# BMS_watchdog.net
KiCad netlist of a schematic drawn in EAGLE
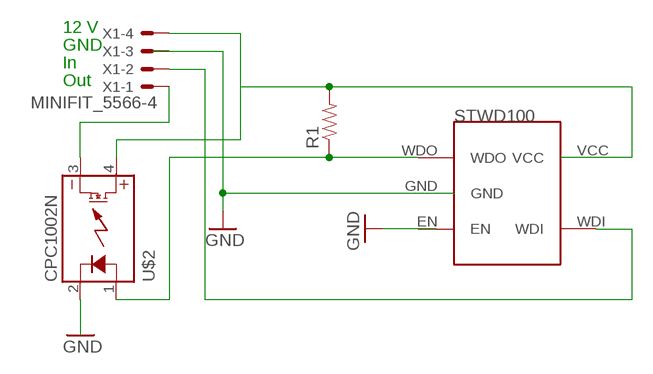
[diagram p0: schematic, sheet 1]

(export (version "E")
  (design (tool "Eeschema 10.0.6"))
  (components
    (comp (ref "R1")
      (value "RESISTOR0805-RES")
      (footprint "eagle-import:0805")
      (libsource (lib "eagle-import") (part "RESISTOR0805-RES"))
    )
    (comp (ref "U$1")
      (value "STWD100")
      (footprint "eagle-import:SOT23-5")
      (libsource (lib "eagle-import") (part "STWD100"))
    )
    (comp (ref "U$2")
      (value "CPC1002N")
      (footprint "eagle-import:SOP04")
      (libsource (lib "eagle-import") (part "CPC1002N"))
    )
    (comp (ref "X1")
      (value "MINIFIT_5566-4")
      (footprint "eagle-import:MINIFIT_5566-4")
      (libsource (lib "eagle-import") (part "MINIFIT_5566-4"))
    )
  )
  (nets
    (net (code "2") (name "Net-(U$2-CONTROL+)") (class "Default")
      (node (ref "R1") (pin "1") (pinfunction "1_1") (pintype "passive"))
      (node (ref "U$1") (pin "WDO") (pinfunction "WDO_WDO") (pintype "bidirectional"))
      (node (ref "U$2") (pin "1") (pinfunction "CONTROL+_1") (pintype "passive"))
    )
    (net (code "3") (name "Net-(U$2-DC+)") (class "Default")
      (node (ref "R1") (pin "2") (pinfunction "2_2") (pintype "passive"))
      (node (ref "U$2") (pin "4") (pinfunction "DC+_4") (pintype "passive"))
      (node (ref "X1") (pin "4") (pinfunction "S_4") (pintype "passive"))
    )
    (net (code "4") (name "Net-(U$2-DC-)") (class "Default")
      (node (ref "U$2") (pin "3") (pinfunction "DC-_3") (pintype "passive"))
      (node (ref "X1") (pin "1") (pinfunction "S_1") (pintype "passive"))
    )
    (net (code "5") (name "Net-(X1B-S)") (class "Default")
      (node (ref "U$1") (pin "WDI") (pinfunction "WDI_WDI") (pintype "bidirectional"))
      (node (ref "X1") (pin "2") (pinfunction "S_2") (pintype "passive"))
    )
    (net (code "6") (name "unconnected-(U$1-PadEN)") (class "Default")
      (node (ref "U$1") (pin "EN") (pinfunction "EN_EN") (pintype "bidirectional"))
    )
    (net (code "7") (name "unconnected-(U$1-PadGND)") (class "Default")
      (node (ref "U$1") (pin "GND") (pinfunction "GND_GND") (pintype "bidirectional"))
    )
    (net (code "8") (name "unconnected-(U$1-PadVCC)") (class "Default")
      (node (ref "U$1") (pin "VCC") (pinfunction "VCC_VCC") (pintype "bidirectional"))
    )
    (net (code "9") (name "unconnected-(U$2-CONTROL--Pad2)") (class "Default")
      (node (ref "U$2") (pin "2") (pinfunction "CONTROL-_2") (pintype "passive"))
    )
    (net (code "10") (name "unconnected-(X1C-S-Pad3)") (class "Default")
      (node (ref "X1") (pin "3") (pinfunction "S_3") (pintype "passive"))
    )
  )
)
